# T-connect.net
KiCad netlist of a schematic drawn in EAGLE
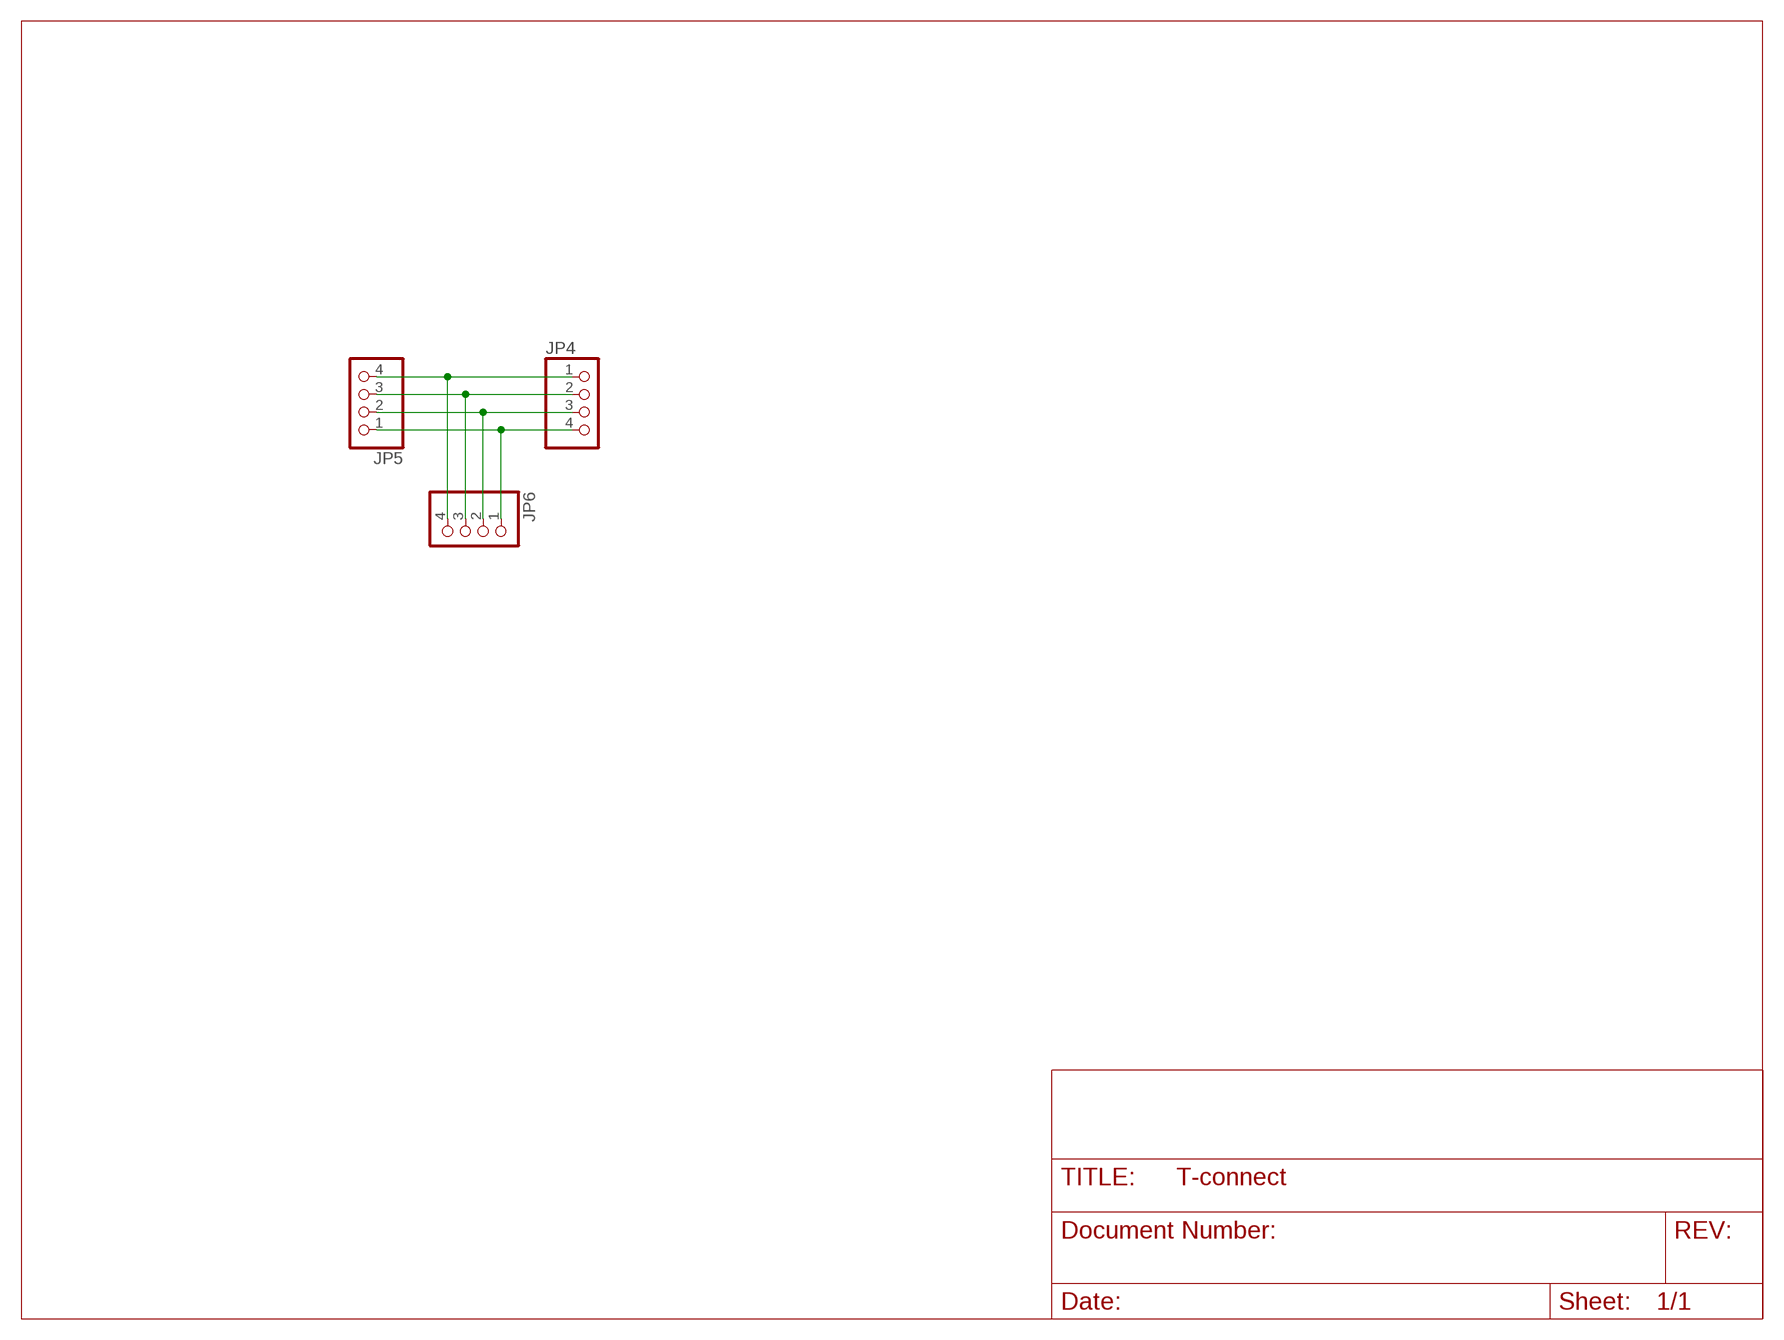
[diagram p0: schematic, sheet 1]

(export (version "E")
  (design (tool "Eeschema 10.0.6"))
  (components
    (comp (ref "JP4")
      (value "PINHD-1X4/90")
      (footprint "eagle-import:1X04_90")
      (libsource (lib "eagle-import") (part "PINHD-1X4/90"))
    )
    (comp (ref "JP5")
      (value "PINHD-1X4/90")
      (footprint "eagle-import:1X04_90")
      (libsource (lib "eagle-import") (part "PINHD-1X4/90"))
    )
    (comp (ref "JP6")
      (value "PINHD-1X4/90")
      (footprint "eagle-import:1X04_90")
      (libsource (lib "eagle-import") (part "PINHD-1X4/90"))
    )
  )
  (nets
    (net (code "1") (name "Net-(JP4-Pad1)") (class "Default")
      (node (ref "JP4") (pin "1") (pinfunction "1_1") (pintype "passive"))
      (node (ref "JP5") (pin "4") (pinfunction "4_4") (pintype "passive"))
      (node (ref "JP6") (pin "4") (pinfunction "4_4") (pintype "passive"))
    )
    (net (code "2") (name "Net-(JP4-Pad2)") (class "Default")
      (node (ref "JP4") (pin "2") (pinfunction "2_2") (pintype "passive"))
      (node (ref "JP5") (pin "3") (pinfunction "3_3") (pintype "passive"))
      (node (ref "JP6") (pin "3") (pinfunction "3_3") (pintype "passive"))
    )
    (net (code "3") (name "Net-(JP4-Pad3)") (class "Default")
      (node (ref "JP4") (pin "3") (pinfunction "3_3") (pintype "passive"))
      (node (ref "JP5") (pin "2") (pinfunction "2_2") (pintype "passive"))
      (node (ref "JP6") (pin "2") (pinfunction "2_2") (pintype "passive"))
    )
    (net (code "4") (name "Net-(JP4-Pad4)") (class "Default")
      (node (ref "JP4") (pin "4") (pinfunction "4_4") (pintype "passive"))
      (node (ref "JP5") (pin "1") (pinfunction "1_1") (pintype "passive"))
      (node (ref "JP6") (pin "1") (pinfunction "1_1") (pintype "passive"))
    )
  )
)
